# rc2014_template.net
KiCad netlist of a schematic drawn in EAGLE
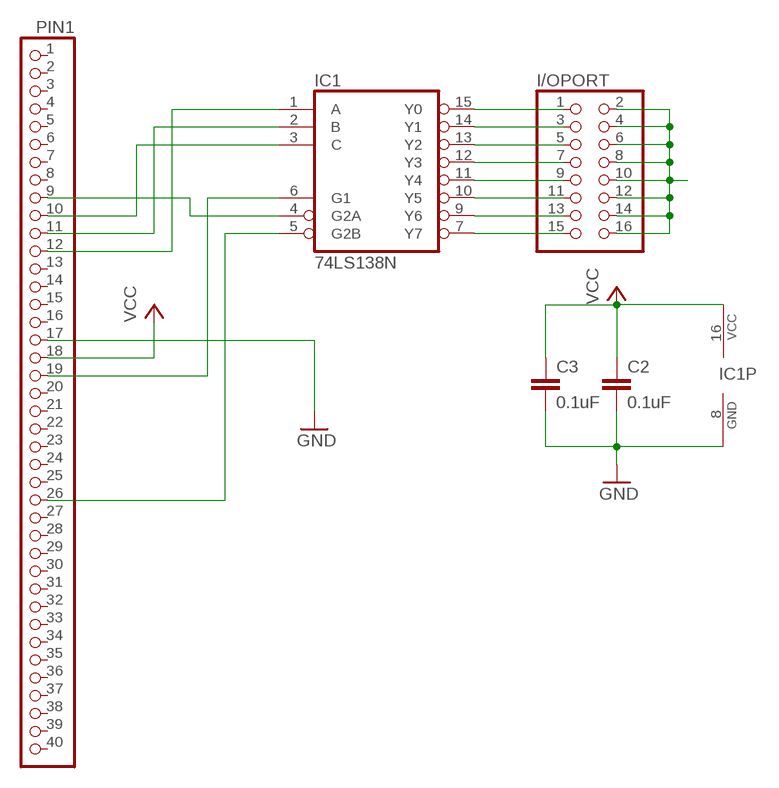
[diagram p0: schematic, sheet 1]

(export (version "E")
  (design (tool "Eeschema 10.0.6"))
  (components
    (comp (ref "C2")
      (value "0.1uF")
      (footprint "eagle-import:C050-024X044")
      (libsource (lib "eagle-import") (part "C-EU050-024X044"))
    )
    (comp (ref "C3")
      (value "0.1uF")
      (footprint "eagle-import:C050-024X044")
      (libsource (lib "eagle-import") (part "C-EU050-024X044"))
    )
    (comp (ref "I/OPORT")
      (value "PINHD-2X8")
      (footprint "eagle-import:2X08")
      (libsource (lib "eagle-import") (part "PINHD-2X8"))
    )
    (comp (ref "IC1")
      (value "74LS138N")
      (footprint "eagle-import:DIL16")
      (libsource (lib "eagle-import") (part "74138NLS"))
    )
    (comp (ref "PIN1")
      (value "PINHD-1X40")
      (footprint "eagle-import:1X40")
      (libsource (lib "eagle-import") (part "PINHD-1X40"))
    )
  )
  (nets
    (net (code "1") (name "GND") (class "Default")
      (node (ref "C2") (pin "2") (pinfunction "2_2") (pintype "passive"))
      (node (ref "C3") (pin "2") (pinfunction "2_2") (pintype "passive"))
      (node (ref "IC1") (pin "8") (pinfunction "GND_8") (pintype "power_in"))
      (node (ref "PIN1") (pin "17") (pinfunction "17_17") (pintype "passive"))
    )
    (net (code "2") (name "Net-(I/OPORT-Pad10)") (class "Default")
      (node (ref "I/OPORT") (pin "10") (pinfunction "10_10") (pintype "passive"))
      (node (ref "I/OPORT") (pin "12") (pinfunction "12_12") (pintype "passive"))
      (node (ref "I/OPORT") (pin "14") (pinfunction "14_14") (pintype "passive"))
      (node (ref "I/OPORT") (pin "16") (pinfunction "16_16") (pintype "passive"))
      (node (ref "I/OPORT") (pin "2") (pinfunction "2_2") (pintype "passive"))
      (node (ref "I/OPORT") (pin "4") (pinfunction "4_4") (pintype "passive"))
      (node (ref "I/OPORT") (pin "6") (pinfunction "6_6") (pintype "passive"))
      (node (ref "I/OPORT") (pin "8") (pinfunction "8_8") (pintype "passive"))
    )
    (net (code "3") (name "Net-(IC1A-A)") (class "Default")
      (node (ref "IC1") (pin "1") (pinfunction "A_1") (pintype "input"))
      (node (ref "PIN1") (pin "12") (pinfunction "12_12") (pintype "passive"))
    )
    (net (code "4") (name "Net-(IC1A-B)") (class "Default")
      (node (ref "IC1") (pin "2") (pinfunction "B_2") (pintype "input"))
      (node (ref "PIN1") (pin "11") (pinfunction "11_11") (pintype "passive"))
    )
    (net (code "5") (name "Net-(IC1A-C)") (class "Default")
      (node (ref "IC1") (pin "3") (pinfunction "C_3") (pintype "input"))
      (node (ref "PIN1") (pin "10") (pinfunction "10_10") (pintype "passive"))
    )
    (net (code "6") (name "Net-(IC1A-G1)") (class "Default")
      (node (ref "IC1") (pin "6") (pinfunction "G1_6") (pintype "input"))
      (node (ref "PIN1") (pin "19") (pinfunction "19_19") (pintype "passive"))
    )
    (net (code "7") (name "Net-(IC1A-G2A)") (class "Default")
      (node (ref "IC1") (pin "4") (pinfunction "G2A_4") (pintype "input"))
      (node (ref "PIN1") (pin "9") (pinfunction "9_9") (pintype "passive"))
    )
    (net (code "8") (name "Net-(IC1A-G2B)") (class "Default")
      (node (ref "IC1") (pin "5") (pinfunction "G2B_5") (pintype "input"))
      (node (ref "PIN1") (pin "26") (pinfunction "26_26") (pintype "passive"))
    )
    (net (code "9") (name "Net-(IC1A-Y0)") (class "Default")
      (node (ref "I/OPORT") (pin "1") (pinfunction "1_1") (pintype "passive"))
      (node (ref "IC1") (pin "15") (pinfunction "Y0_15") (pintype "output"))
    )
    (net (code "10") (name "Net-(IC1A-Y1)") (class "Default")
      (node (ref "I/OPORT") (pin "3") (pinfunction "3_3") (pintype "passive"))
      (node (ref "IC1") (pin "14") (pinfunction "Y1_14") (pintype "output"))
    )
    (net (code "11") (name "Net-(IC1A-Y2)") (class "Default")
      (node (ref "I/OPORT") (pin "5") (pinfunction "5_5") (pintype "passive"))
      (node (ref "IC1") (pin "13") (pinfunction "Y2_13") (pintype "output"))
    )
    (net (code "12") (name "Net-(IC1A-Y3)") (class "Default")
      (node (ref "I/OPORT") (pin "7") (pinfunction "7_7") (pintype "passive"))
      (node (ref "IC1") (pin "12") (pinfunction "Y3_12") (pintype "output"))
    )
    (net (code "13") (name "Net-(IC1A-Y4)") (class "Default")
      (node (ref "I/OPORT") (pin "9") (pinfunction "9_9") (pintype "passive"))
      (node (ref "IC1") (pin "11") (pinfunction "Y4_11") (pintype "output"))
    )
    (net (code "14") (name "Net-(IC1A-Y5)") (class "Default")
      (node (ref "I/OPORT") (pin "11") (pinfunction "11_11") (pintype "passive"))
      (node (ref "IC1") (pin "10") (pinfunction "Y5_10") (pintype "output"))
    )
    (net (code "15") (name "Net-(IC1A-Y6)") (class "Default")
      (node (ref "I/OPORT") (pin "13") (pinfunction "13_13") (pintype "passive"))
      (node (ref "IC1") (pin "9") (pinfunction "Y6_9") (pintype "output"))
    )
    (net (code "16") (name "Net-(IC1A-Y7)") (class "Default")
      (node (ref "I/OPORT") (pin "15") (pinfunction "15_15") (pintype "passive"))
      (node (ref "IC1") (pin "7") (pinfunction "Y7_7") (pintype "output"))
    )
    (net (code "17") (name "VCC") (class "Default")
      (node (ref "C2") (pin "1") (pinfunction "1_1") (pintype "passive"))
      (node (ref "C3") (pin "1") (pinfunction "1_1") (pintype "passive"))
      (node (ref "IC1") (pin "16") (pinfunction "VCC_16") (pintype "power_in"))
      (node (ref "PIN1") (pin "18") (pinfunction "18_18") (pintype "passive"))
    )
    (net (code "18") (name "unconnected-(PIN1-Pad1)") (class "Default")
      (node (ref "PIN1") (pin "1") (pinfunction "1_1") (pintype "passive"))
    )
    (net (code "19") (name "unconnected-(PIN1-Pad2)") (class "Default")
      (node (ref "PIN1") (pin "2") (pinfunction "2_2") (pintype "passive"))
    )
    (net (code "20") (name "unconnected-(PIN1-Pad3)") (class "Default")
      (node (ref "PIN1") (pin "3") (pinfunction "3_3") (pintype "passive"))
    )
    (net (code "21") (name "unconnected-(PIN1-Pad4)") (class "Default")
      (node (ref "PIN1") (pin "4") (pinfunction "4_4") (pintype "passive"))
    )
    (net (code "22") (name "unconnected-(PIN1-Pad5)") (class "Default")
      (node (ref "PIN1") (pin "5") (pinfunction "5_5") (pintype "passive"))
    )
    (net (code "23") (name "unconnected-(PIN1-Pad6)") (class "Default")
      (node (ref "PIN1") (pin "6") (pinfunction "6_6") (pintype "passive"))
    )
    (net (code "24") (name "unconnected-(PIN1-Pad7)") (class "Default")
      (node (ref "PIN1") (pin "7") (pinfunction "7_7") (pintype "passive"))
    )
    (net (code "25") (name "unconnected-(PIN1-Pad8)") (class "Default")
      (node (ref "PIN1") (pin "8") (pinfunction "8_8") (pintype "passive"))
    )
    (net (code "26") (name "unconnected-(PIN1-Pad13)") (class "Default")
      (node (ref "PIN1") (pin "13") (pinfunction "13_13") (pintype "passive"))
    )
    (net (code "27") (name "unconnected-(PIN1-Pad14)") (class "Default")
      (node (ref "PIN1") (pin "14") (pinfunction "14_14") (pintype "passive"))
    )
    (net (code "28") (name "unconnected-(PIN1-Pad15)") (class "Default")
      (node (ref "PIN1") (pin "15") (pinfunction "15_15") (pintype "passive"))
    )
    (net (code "29") (name "unconnected-(PIN1-Pad16)") (class "Default")
      (node (ref "PIN1") (pin "16") (pinfunction "16_16") (pintype "passive"))
    )
    (net (code "30") (name "unconnected-(PIN1-Pad20)") (class "Default")
      (node (ref "PIN1") (pin "20") (pinfunction "20_20") (pintype "passive"))
    )
    (net (code "31") (name "unconnected-(PIN1-Pad21)") (class "Default")
      (node (ref "PIN1") (pin "21") (pinfunction "21_21") (pintype "passive"))
    )
    (net (code "32") (name "unconnected-(PIN1-Pad22)") (class "Default")
      (node (ref "PIN1") (pin "22") (pinfunction "22_22") (pintype "passive"))
    )
    (net (code "33") (name "unconnected-(PIN1-Pad23)") (class "Default")
      (node (ref "PIN1") (pin "23") (pinfunction "23_23") (pintype "passive"))
    )
    (net (code "34") (name "unconnected-(PIN1-Pad24)") (class "Default")
      (node (ref "PIN1") (pin "24") (pinfunction "24_24") (pintype "passive"))
    )
    (net (code "35") (name "unconnected-(PIN1-Pad25)") (class "Default")
      (node (ref "PIN1") (pin "25") (pinfunction "25_25") (pintype "passive"))
    )
    (net (code "36") (name "unconnected-(PIN1-Pad27)") (class "Default")
      (node (ref "PIN1") (pin "27") (pinfunction "27_27") (pintype "passive"))
    )
    (net (code "37") (name "unconnected-(PIN1-Pad28)") (class "Default")
      (node (ref "PIN1") (pin "28") (pinfunction "28_28") (pintype "passive"))
    )
    (net (code "38") (name "unconnected-(PIN1-Pad29)") (class "Default")
      (node (ref "PIN1") (pin "29") (pinfunction "29_29") (pintype "passive"))
    )
    (net (code "39") (name "unconnected-(PIN1-Pad30)") (class "Default")
      (node (ref "PIN1") (pin "30") (pinfunction "30_30") (pintype "passive"))
    )
    (net (code "40") (name "unconnected-(PIN1-Pad31)") (class "Default")
      (node (ref "PIN1") (pin "31") (pinfunction "31_31") (pintype "passive"))
    )
    (net (code "41") (name "unconnected-(PIN1-Pad32)") (class "Default")
      (node (ref "PIN1") (pin "32") (pinfunction "32_32") (pintype "passive"))
    )
    (net (code "42") (name "unconnected-(PIN1-Pad33)") (class "Default")
      (node (ref "PIN1") (pin "33") (pinfunction "33_33") (pintype "passive"))
    )
    (net (code "43") (name "unconnected-(PIN1-Pad34)") (class "Default")
      (node (ref "PIN1") (pin "34") (pinfunction "34_34") (pintype "passive"))
    )
    (net (code "44") (name "unconnected-(PIN1-Pad35)") (class "Default")
      (node (ref "PIN1") (pin "35") (pinfunction "35_35") (pintype "passive"))
    )
    (net (code "45") (name "unconnected-(PIN1-Pad36)") (class "Default")
      (node (ref "PIN1") (pin "36") (pinfunction "36_36") (pintype "passive"))
    )
    (net (code "46") (name "unconnected-(PIN1-Pad37)") (class "Default")
      (node (ref "PIN1") (pin "37") (pinfunction "37_37") (pintype "passive"))
    )
    (net (code "47") (name "unconnected-(PIN1-Pad38)") (class "Default")
      (node (ref "PIN1") (pin "38") (pinfunction "38_38") (pintype "passive"))
    )
    (net (code "48") (name "unconnected-(PIN1-Pad39)") (class "Default")
      (node (ref "PIN1") (pin "39") (pinfunction "39_39") (pintype "passive"))
    )
    (net (code "49") (name "unconnected-(PIN1-Pad40)") (class "Default")
      (node (ref "PIN1") (pin "40") (pinfunction "40_40") (pintype "passive"))
    )
  )
)
